# Xbee_SHT71_Shield.net
KiCad netlist of a schematic drawn in EAGLE
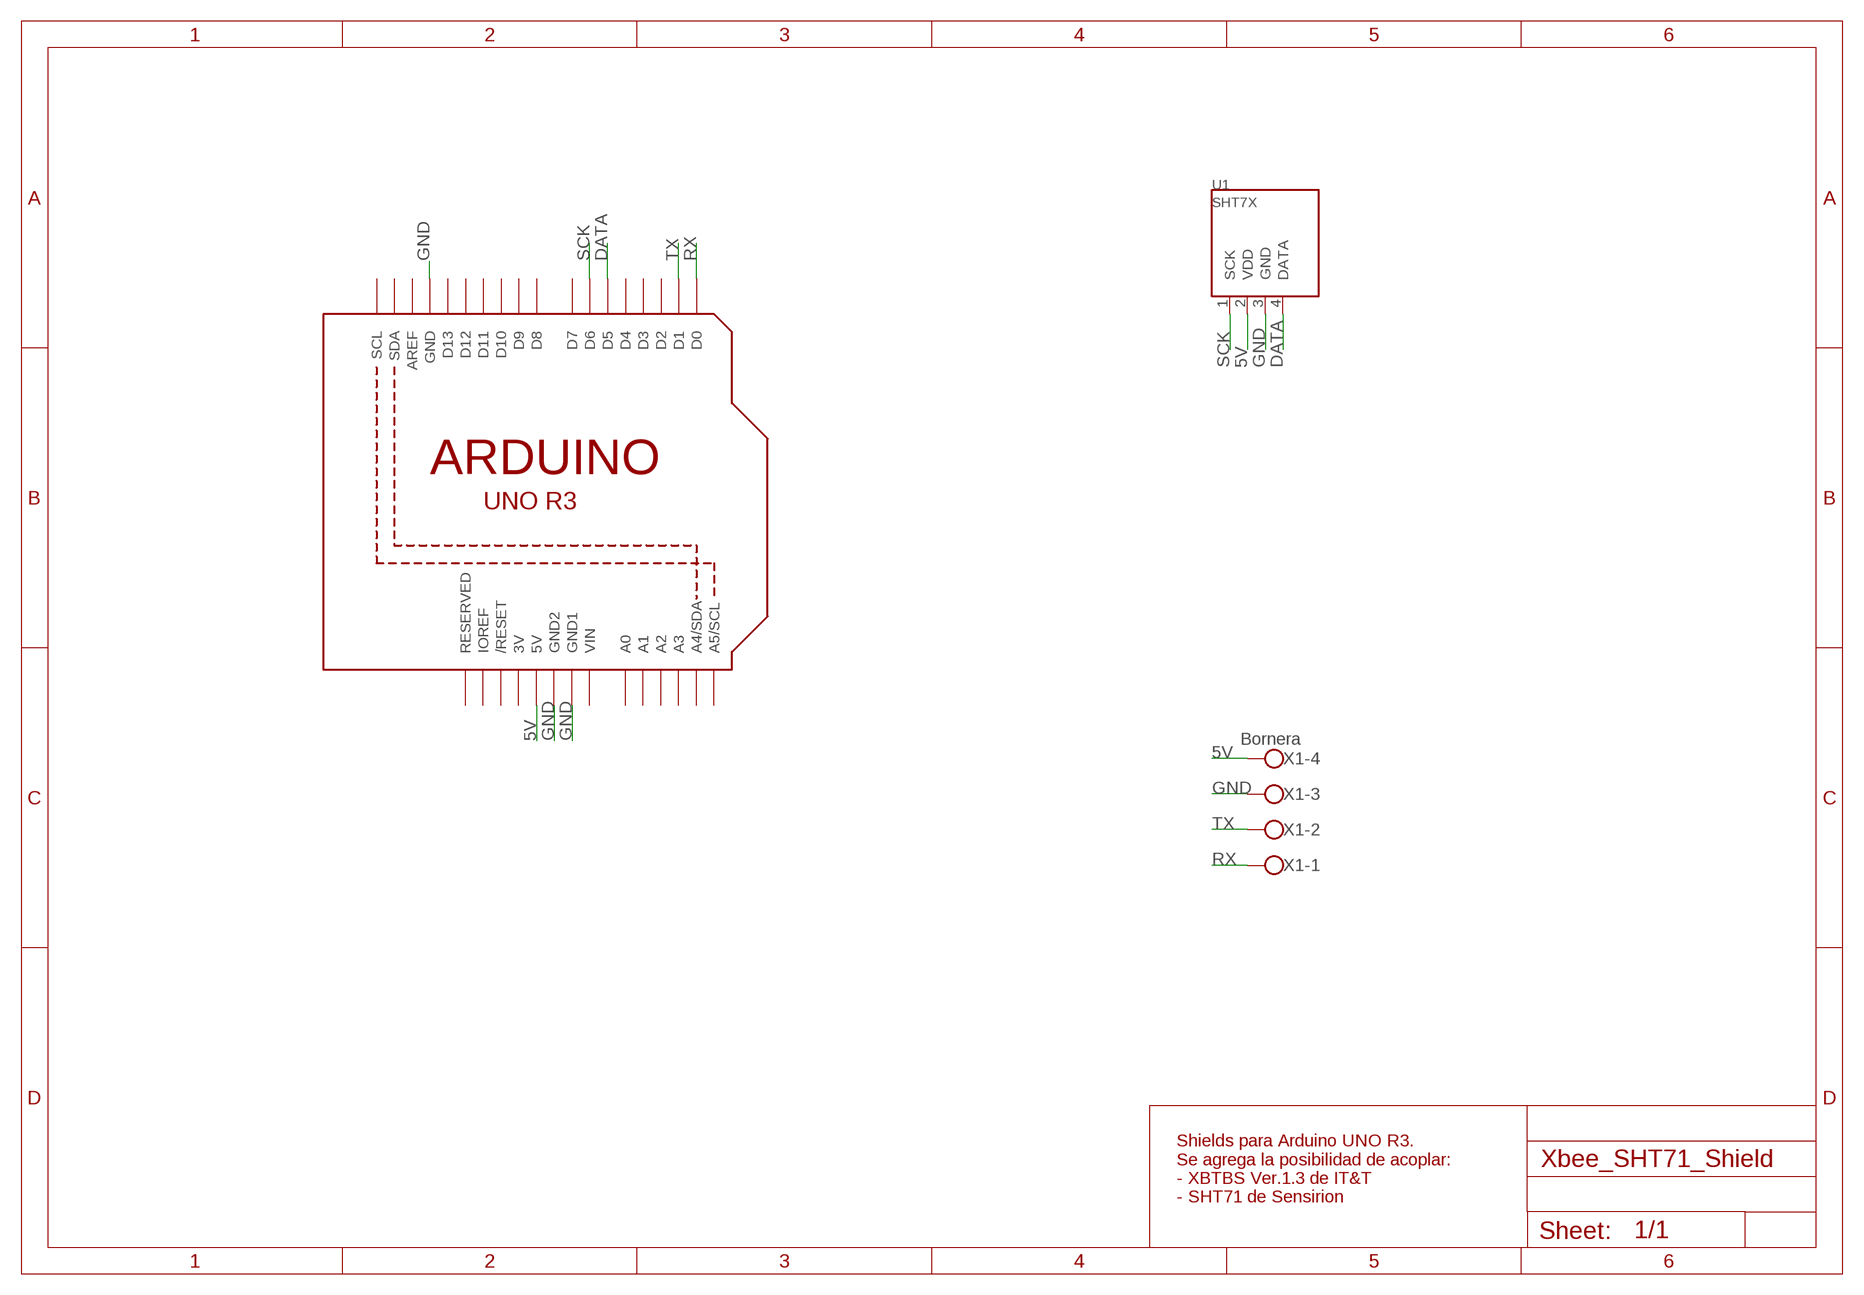
[diagram p0: schematic, sheet 1]

(export (version "E")
  (design (tool "Eeschema 10.0.6"))
  (components
    (comp (ref "U1")
      (value "SHT7X")
      (footprint "eagle-import:SHT7X")
      (libsource (lib "eagle-import") (part "SHT7X"))
    )
    (comp (ref "U2")
      (value "ARDUINOR3-DIMENSION")
      (footprint "eagle-import:ARDUINOR3")
      (libsource (lib "eagle-import") (part "ARDUINOR3-DIMENSION"))
    )
    (comp (ref "X1")
      (value "Bornera")
      (footprint "eagle-import:W237-4")
      (libsource (lib "eagle-import") (part "W237-4"))
    )
  )
  (nets
    (net (code "1") (name "/3V") (class "Default")
      (node (ref "U2") (pin "3V") (pinfunction "3V_3V") (pintype "power_in"))
    )
    (net (code "2") (name "/5V") (class "Default")
      (node (ref "U1") (pin "2") (pinfunction "VDD_2") (pintype "power_in"))
      (node (ref "U2") (pin "5V") (pinfunction "5V_5V") (pintype "power_in"))
      (node (ref "X1") (pin "4") (pinfunction "KL_4") (pintype "passive"))
    )
    (net (code "3") (name "/DATA") (class "Default")
      (node (ref "U1") (pin "4") (pinfunction "DATA_4") (pintype "bidirectional"))
      (node (ref "U2") (pin "D5") (pinfunction "D5_D5") (pintype "bidirectional"))
    )
    (net (code "4") (name "/GND") (class "Default")
      (node (ref "U1") (pin "3") (pinfunction "GND_3") (pintype "power_in"))
      (node (ref "U2") (pin "GND") (pinfunction "GND_GND") (pintype "power_in"))
      (node (ref "U2") (pin "GND1") (pinfunction "GND1_GND1") (pintype "power_in"))
      (node (ref "U2") (pin "GND2") (pinfunction "GND2_GND2") (pintype "power_in"))
      (node (ref "X1") (pin "3") (pinfunction "KL_3") (pintype "passive"))
    )
    (net (code "5") (name "/RX") (class "Default")
      (node (ref "U2") (pin "D0") (pinfunction "D0_D0") (pintype "bidirectional"))
      (node (ref "X1") (pin "1") (pinfunction "KL_1") (pintype "passive"))
    )
    (net (code "6") (name "/SCK") (class "Default")
      (node (ref "U1") (pin "1") (pinfunction "SCK_1") (pintype "bidirectional"))
      (node (ref "U2") (pin "D6") (pinfunction "D6_D6") (pintype "bidirectional"))
    )
    (net (code "7") (name "/TX") (class "Default")
      (node (ref "U2") (pin "D1") (pinfunction "D1_D1") (pintype "bidirectional"))
      (node (ref "X1") (pin "2") (pinfunction "KL_2") (pintype "passive"))
    )
    (net (code "8") (name "/VIN") (class "Default")
      (node (ref "U2") (pin "VIN") (pinfunction "VIN_VIN") (pintype "power_in"))
    )
    (net (code "9") (name "unconnected-(U2-A4{slash}SDA-PadA4)") (class "Default")
      (node (ref "U2") (pin "A4") (pinfunction "A4/SDA_A4") (pintype "bidirectional"))
    )
    (net (code "10") (name "unconnected-(U2-A5{slash}SCL-PadA5)") (class "Default")
      (node (ref "U2") (pin "A5") (pinfunction "A5/SCL_A5") (pintype "bidirectional"))
    )
    (net (code "11") (name "unconnected-(U2-PadA0)") (class "Default")
      (node (ref "U2") (pin "A0") (pinfunction "A0_A0") (pintype "bidirectional"))
    )
    (net (code "12") (name "unconnected-(U2-PadA1)") (class "Default")
      (node (ref "U2") (pin "A1") (pinfunction "A1_A1") (pintype "bidirectional"))
    )
    (net (code "13") (name "unconnected-(U2-PadA2)") (class "Default")
      (node (ref "U2") (pin "A2") (pinfunction "A2_A2") (pintype "bidirectional"))
    )
    (net (code "14") (name "unconnected-(U2-PadA3)") (class "Default")
      (node (ref "U2") (pin "A3") (pinfunction "A3_A3") (pintype "bidirectional"))
    )
    (net (code "15") (name "unconnected-(U2-PadAREF)") (class "Default")
      (node (ref "U2") (pin "AREF") (pinfunction "AREF_AREF") (pintype "bidirectional"))
    )
    (net (code "16") (name "unconnected-(U2-PadD2)") (class "Default")
      (node (ref "U2") (pin "D2") (pinfunction "D2_D2") (pintype "bidirectional"))
    )
    (net (code "17") (name "unconnected-(U2-PadD3)") (class "Default")
      (node (ref "U2") (pin "D3") (pinfunction "D3_D3") (pintype "bidirectional"))
    )
    (net (code "18") (name "unconnected-(U2-PadD4)") (class "Default")
      (node (ref "U2") (pin "D4") (pinfunction "D4_D4") (pintype "bidirectional"))
    )
    (net (code "19") (name "unconnected-(U2-PadD7)") (class "Default")
      (node (ref "U2") (pin "D7") (pinfunction "D7_D7") (pintype "bidirectional"))
    )
    (net (code "20") (name "unconnected-(U2-PadD8)") (class "Default")
      (node (ref "U2") (pin "D8") (pinfunction "D8_D8") (pintype "bidirectional"))
    )
    (net (code "21") (name "unconnected-(U2-PadD9)") (class "Default")
      (node (ref "U2") (pin "D9") (pinfunction "D9_D9") (pintype "bidirectional"))
    )
    (net (code "22") (name "unconnected-(U2-PadD10)") (class "Default")
      (node (ref "U2") (pin "D10") (pinfunction "D10_D10") (pintype "bidirectional"))
    )
    (net (code "23") (name "unconnected-(U2-PadD11)") (class "Default")
      (node (ref "U2") (pin "D11") (pinfunction "D11_D11") (pintype "bidirectional"))
    )
    (net (code "24") (name "unconnected-(U2-PadD12)") (class "Default")
      (node (ref "U2") (pin "D12") (pinfunction "D12_D12") (pintype "bidirectional"))
    )
    (net (code "25") (name "unconnected-(U2-PadD13)") (class "Default")
      (node (ref "U2") (pin "D13") (pinfunction "D13_D13") (pintype "bidirectional"))
    )
    (net (code "26") (name "unconnected-(U2-PadIOREF)") (class "Default")
      (node (ref "U2") (pin "IOREF") (pinfunction "IOREF_IOREF") (pintype "output"))
    )
    (net (code "27") (name "unconnected-(U2-PadRESERVED)") (class "Default")
      (node (ref "U2") (pin "RESERVED") (pinfunction "RESERVED_RESERVED") (pintype "no_connect"))
    )
    (net (code "28") (name "unconnected-(U2-PadSCL)") (class "Default")
      (node (ref "U2") (pin "SCL") (pinfunction "SCL_SCL") (pintype "bidirectional"))
    )
    (net (code "29") (name "unconnected-(U2-PadSDA)") (class "Default")
      (node (ref "U2") (pin "SDA") (pinfunction "SDA_SDA") (pintype "bidirectional"))
    )
    (net (code "30") (name "unconnected-(U2-{slash}RESET-PadRESET)") (class "Default")
      (node (ref "U2") (pin "RESET") (pinfunction "/RESET_RESET") (pintype "bidirectional"))
    )
  )
)
